# SD.net
KiCad netlist of a schematic drawn in Altium Designer
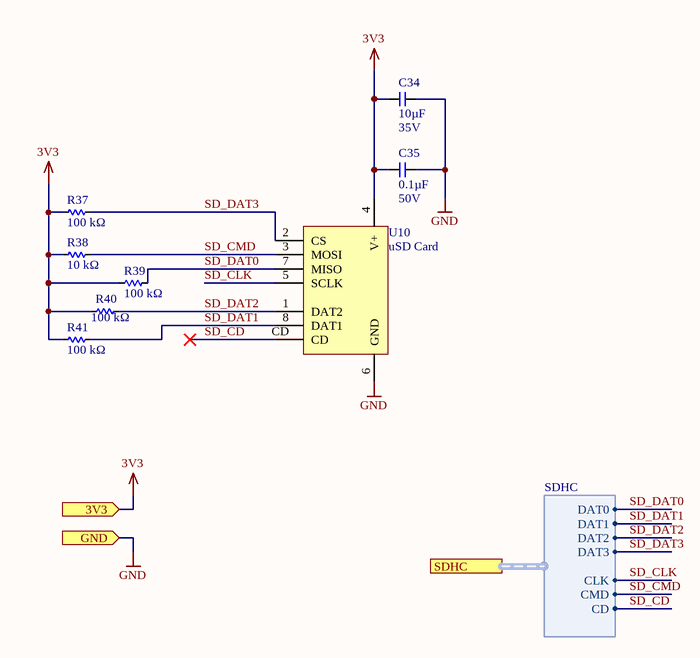
[diagram p0: SD.SchDoc]

(export (version "E")
  (design (tool "Eeschema 10.0.6"))
  (components
    (comp (ref "C34")
      (value "490-13248-1-ND")
      (footprint "C0603")
      (description "CAP CER 10UF 35V X5R 0603 20%")
      (fields
        (field (name "CAPACITANCE (SHORTHAND)") "10µF")
        (field (name "RATED VOLTAGE") "35V")
        (field (name "MANUFACTURER") "Murata Electronics North America")
      )
      (libsource (lib "Stanford Student Space Initiative") (part "__template_cap"))
    )
    (comp (ref "C35")
      (value "490-1519-1-ND")
      (footprint "C0603")
      (description "CAP CER 0603 0.1µF X7R 50V 10%")
      (fields
        (field (name "CAPACITANCE (SHORTHAND)") "0.1µF")
        (field (name "RATED VOLTAGE") "50V")
        (field (name "MANUFACTURER") "Murata Electronics North America")
      )
      (libsource (lib "Stanford Student Space Initiative") (part "__template_cap"))
    )
    (comp (ref "R37")
      (value "311-100KHRCT-ND")
      (footprint "R0603")
      (description "RES SMD 100K OHM 1% 1/10W 0603")
      (fields
        (field (name "RESISTANCE") "100 kΩ")
        (field (name "MANUFACTURER PART NUMBER") "RC0603FR-07100KL")
        (field (name "MANUFACTURER") "Yageo")
      )
      (libsource (lib "Stanford Student Space Initiative") (part "__template_resistor"))
    )
    (comp (ref "R38")
      (value "311-10.0KHRCT-ND")
      (footprint "R0603")
      (description "RES SMD 10K OHM 1% 1/10W 0603")
      (fields
        (field (name "RESISTANCE") "10 kΩ")
        (field (name "MANUFACTURER PART NUMBER") "RC0603FR-0710KL")
        (field (name "MANUFACTURER") "Yageo")
      )
      (libsource (lib "Stanford Student Space Initiative") (part "__template_resistor"))
    )
    (comp (ref "R39")
      (value "311-100KHRCT-ND")
      (footprint "R0603")
      (description "RES SMD 100K OHM 1% 1/10W 0603")
      (fields
        (field (name "RESISTANCE") "100 kΩ")
        (field (name "MANUFACTURER PART NUMBER") "RC0603FR-07100KL")
        (field (name "MANUFACTURER") "Yageo")
      )
      (libsource (lib "Stanford Student Space Initiative") (part "__template_resistor"))
    )
    (comp (ref "R40")
      (value "311-100KHRCT-ND")
      (footprint "R0603")
      (description "RES SMD 100K OHM 1% 1/10W 0603")
      (fields
        (field (name "RESISTANCE") "100 kΩ")
        (field (name "MANUFACTURER PART NUMBER") "RC0603FR-07100KL")
        (field (name "MANUFACTURER") "Yageo")
      )
      (libsource (lib "Stanford Student Space Initiative") (part "__template_resistor"))
    )
    (comp (ref "R41")
      (value "311-100KHRCT-ND")
      (footprint "R0603")
      (description "RES SMD 100K OHM 1% 1/10W 0603")
      (fields
        (field (name "RESISTANCE") "100 kΩ")
        (field (name "MANUFACTURER PART NUMBER") "RC0603FR-07100KL")
        (field (name "MANUFACTURER") "Yageo")
      )
      (libsource (lib "Stanford Student Space Initiative") (part "__template_resistor"))
    )
    (comp (ref "U10")
      (value "uSD Card")
      (footprint "MICROSD_CARD_SOCKET")
      (description "MICROSD CARD HOLDER, PUSH-PUSH")
      (fields (field (name "MANUFACTURER") "3M") (field (name "MANUFACTURER PART NUMBER") "2908-05WB-MG"))
      (libsource (lib "Stanford Student Space Initiative") (part "MICRO_SD_CARD_HOLDER"))
    )
  )
  (nets
    (net (code "2") (name "/SD_CD") (class "Default")
      (node (ref "U10") (pin "CD") (pinfunction "CD_CD") (pintype "passive"))
    )
    (net (code "3") (name "/SD_CLK") (class "Default")
      (node (ref "U10") (pin "5") (pinfunction "SCLK_5") (pintype "passive"))
    )
    (net (code "4") (name "/SD_CMD") (class "Default")
      (node (ref "R38") (pin "2") (pinfunction "2_2") (pintype "passive"))
      (node (ref "U10") (pin "3") (pinfunction "MOSI_3") (pintype "passive"))
    )
    (net (code "5") (name "/SD_DAT0") (class "Default")
      (node (ref "R39") (pin "2") (pinfunction "2_2") (pintype "passive"))
      (node (ref "U10") (pin "7") (pinfunction "MISO_7") (pintype "passive"))
    )
    (net (code "6") (name "/SD_DAT1") (class "Default")
      (node (ref "R41") (pin "2") (pinfunction "2_2") (pintype "passive"))
      (node (ref "U10") (pin "8") (pinfunction "DAT1_8") (pintype "passive"))
    )
    (net (code "7") (name "/SD_DAT2") (class "Default")
      (node (ref "R40") (pin "2") (pinfunction "2_2") (pintype "passive"))
      (node (ref "U10") (pin "1") (pinfunction "DAT2_1") (pintype "passive"))
    )
    (net (code "8") (name "/SD_DAT3") (class "Default")
      (node (ref "R37") (pin "2") (pinfunction "2_2") (pintype "passive"))
      (node (ref "U10") (pin "2") (pinfunction "CS_2") (pintype "passive"))
    )
    (net (code "10") (name "3V3") (class "Default")
      (node (ref "C34") (pin "2") (pintype "passive"))
      (node (ref "C35") (pin "1") (pintype "passive"))
      (node (ref "R37") (pin "1") (pinfunction "1_1") (pintype "passive"))
      (node (ref "R38") (pin "1") (pinfunction "1_1") (pintype "passive"))
      (node (ref "R39") (pin "1") (pinfunction "1_1") (pintype "passive"))
      (node (ref "R40") (pin "1") (pinfunction "1_1") (pintype "passive"))
      (node (ref "R41") (pin "1") (pinfunction "1_1") (pintype "passive"))
      (node (ref "U10") (pin "4") (pinfunction "V+_4") (pintype "passive"))
    )
    (net (code "11") (name "GND") (class "Default")
      (node (ref "C34") (pin "1") (pintype "passive"))
      (node (ref "C35") (pin "2") (pintype "passive"))
      (node (ref "U10") (pin "6") (pinfunction "GND_6") (pintype "passive"))
    )
  )
)
